# PMI_Action_bumpers.net
KiCad netlist of a schematic drawn in Altium Designer
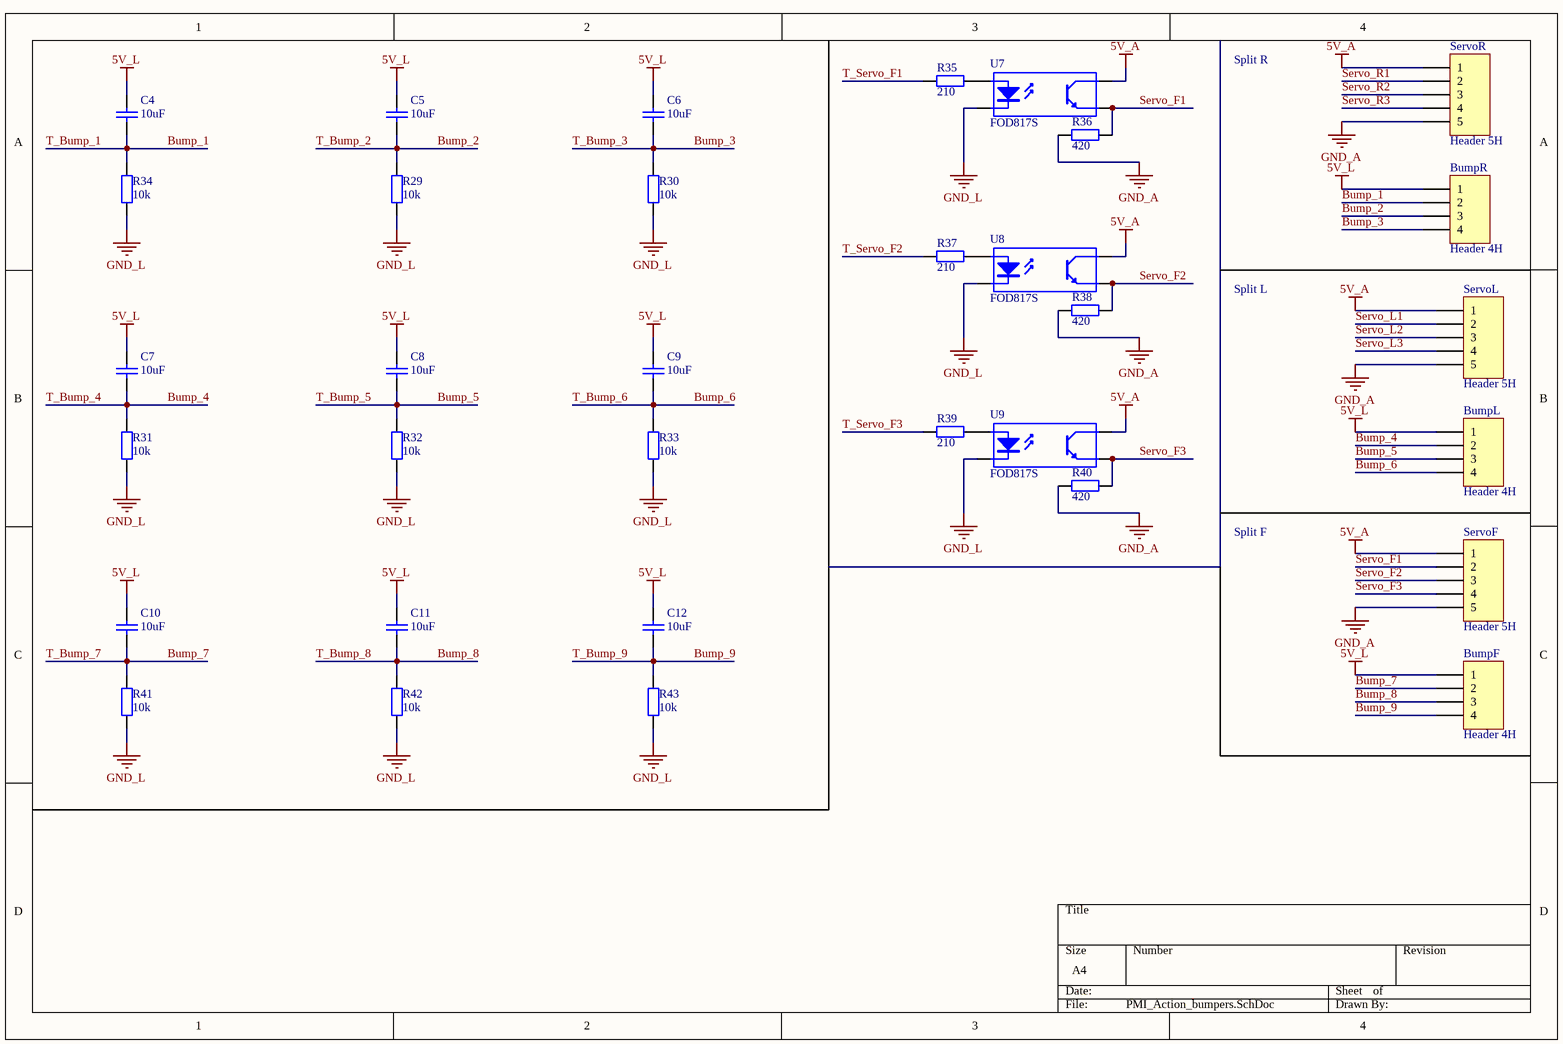
[diagram p0: PMI_Action_bumpers.SchDoc]

(export (version "E")
  (design (tool "Eeschema 10.0.6"))
  (components
    (comp (ref "BumpF")
      (value "Header 4H")
      (footprint "S4B-XH-A")
      (description "Header, 4-Pin, Right Angle")
      (fields (field (name "PUBLISHER") "Altium Limited"))
      (libsource (lib "Miscellaneous Connectors") (part "Header 4H"))
    )
    (comp (ref "BumpL")
      (value "Header 4H")
      (footprint "S4B-XH-A")
      (description "Header, 4-Pin, Right Angle")
      (fields (field (name "PUBLISHER") "Altium Limited"))
      (libsource (lib "Miscellaneous Connectors") (part "Header 4H"))
    )
    (comp (ref "BumpR")
      (value "Header 4H")
      (footprint "S4B-XH-A")
      (description "Header, 4-Pin, Right Angle")
      (fields (field (name "PUBLISHER") "Altium Limited"))
      (libsource (lib "Miscellaneous Connectors") (part "Header 4H"))
    )
    (comp (ref "C4")
      (value "10uF")
      (footprint "Capacitor 1206")
      (description "Capacitor")
      (fields (field (name "Comment") "(optional)") (field (name "PUBLISHER") "Altium Limited"))
      (libsource (lib "Miscellaneous Devices") (part "Cap"))
    )
    (comp (ref "C5")
      (value "10uF")
      (footprint "Capacitor 1206")
      (description "Capacitor")
      (fields (field (name "Comment") "(optional)") (field (name "PUBLISHER") "Altium Limited"))
      (libsource (lib "Miscellaneous Devices") (part "Cap"))
    )
    (comp (ref "C6")
      (value "10uF")
      (footprint "Capacitor 1206")
      (description "Capacitor")
      (fields (field (name "Comment") "(optional)") (field (name "PUBLISHER") "Altium Limited"))
      (libsource (lib "Miscellaneous Devices") (part "Cap"))
    )
    (comp (ref "C7")
      (value "10uF")
      (footprint "Capacitor 1206")
      (description "Capacitor")
      (fields (field (name "Comment") "(optional)") (field (name "PUBLISHER") "Altium Limited"))
      (libsource (lib "Miscellaneous Devices") (part "Cap"))
    )
    (comp (ref "C8")
      (value "10uF")
      (footprint "Capacitor 1206")
      (description "Capacitor")
      (fields (field (name "Comment") "(optional)") (field (name "PUBLISHER") "Altium Limited"))
      (libsource (lib "Miscellaneous Devices") (part "Cap"))
    )
    (comp (ref "C9")
      (value "10uF")
      (footprint "Capacitor 1206")
      (description "Capacitor")
      (fields (field (name "Comment") "(optional)") (field (name "PUBLISHER") "Altium Limited"))
      (libsource (lib "Miscellaneous Devices") (part "Cap"))
    )
    (comp (ref "C10")
      (value "10uF")
      (footprint "Capacitor 1206")
      (description "Capacitor")
      (fields (field (name "Comment") "(optional)") (field (name "PUBLISHER") "Altium Limited"))
      (libsource (lib "Miscellaneous Devices") (part "Cap"))
    )
    (comp (ref "C11")
      (value "10uF")
      (footprint "Capacitor 1206")
      (description "Capacitor")
      (fields (field (name "Comment") "(optional)") (field (name "PUBLISHER") "Altium Limited"))
      (libsource (lib "Miscellaneous Devices") (part "Cap"))
    )
    (comp (ref "C12")
      (value "10uF")
      (footprint "Capacitor 1206")
      (description "Capacitor")
      (fields (field (name "Comment") "(optional)") (field (name "PUBLISHER") "Altium Limited"))
      (libsource (lib "Miscellaneous Devices") (part "Cap"))
    )
    (comp (ref "R29")
      (value "10k")
      (footprint "Resistor 1206")
      (description "Resistor")
      (fields (field (name "Comment") "Res2") (field (name "PUBLISHER") "Altium Limited"))
      (libsource (lib "Miscellaneous Devices") (part "Res2"))
    )
    (comp (ref "R30")
      (value "10k")
      (footprint "Resistor 1206")
      (description "Resistor")
      (fields (field (name "Comment") "Res2") (field (name "PUBLISHER") "Altium Limited"))
      (libsource (lib "Miscellaneous Devices") (part "Res2"))
    )
    (comp (ref "R31")
      (value "10k")
      (footprint "Resistor 1206")
      (description "Resistor")
      (fields (field (name "Comment") "Res2") (field (name "PUBLISHER") "Altium Limited"))
      (libsource (lib "Miscellaneous Devices") (part "Res2"))
    )
    (comp (ref "R32")
      (value "10k")
      (footprint "Resistor 1206")
      (description "Resistor")
      (fields (field (name "Comment") "Res2") (field (name "PUBLISHER") "Altium Limited"))
      (libsource (lib "Miscellaneous Devices") (part "Res2"))
    )
    (comp (ref "R33")
      (value "10k")
      (footprint "Resistor 1206")
      (description "Resistor")
      (fields (field (name "Comment") "Res2") (field (name "PUBLISHER") "Altium Limited"))
      (libsource (lib "Miscellaneous Devices") (part "Res2"))
    )
    (comp (ref "R34")
      (value "10k")
      (footprint "Resistor 1206")
      (description "Resistor")
      (fields (field (name "Comment") "Res2") (field (name "PUBLISHER") "Altium Limited"))
      (libsource (lib "Miscellaneous Devices") (part "Res2"))
    )
    (comp (ref "R35")
      (value "210")
      (footprint "Resistor 1206")
      (description "Resistor")
      (fields (field (name "Comment") "Res2") (field (name "PUBLISHER") "Altium Limited"))
      (libsource (lib "") (part "Res2_1"))
    )
    (comp (ref "R36")
      (value "420")
      (footprint "Resistor 1206")
      (description "Resistor")
      (fields (field (name "Comment") "Res2") (field (name "PUBLISHER") "Altium Limited"))
      (libsource (lib "") (part "Res2_1"))
    )
    (comp (ref "R37")
      (value "210")
      (footprint "Resistor 1206")
      (description "Resistor")
      (fields (field (name "Comment") "Res2") (field (name "PUBLISHER") "Altium Limited"))
      (libsource (lib "") (part "Res2_1"))
    )
    (comp (ref "R38")
      (value "420")
      (footprint "Resistor 1206")
      (description "Resistor")
      (fields (field (name "Comment") "Res2") (field (name "PUBLISHER") "Altium Limited"))
      (libsource (lib "") (part "Res2_1"))
    )
    (comp (ref "R39")
      (value "210")
      (footprint "Resistor 1206")
      (description "Resistor")
      (fields (field (name "Comment") "Res2") (field (name "PUBLISHER") "Altium Limited"))
      (libsource (lib "") (part "Res2_1"))
    )
    (comp (ref "R40")
      (value "420")
      (footprint "Resistor 1206")
      (description "Resistor")
      (fields (field (name "Comment") "Res2") (field (name "PUBLISHER") "Altium Limited"))
      (libsource (lib "") (part "Res2_1"))
    )
    (comp (ref "R41")
      (value "10k")
      (footprint "Resistor 1206")
      (description "Resistor")
      (fields (field (name "Comment") "Res2") (field (name "PUBLISHER") "Altium Limited"))
      (libsource (lib "Miscellaneous Devices") (part "Res2"))
    )
    (comp (ref "R42")
      (value "10k")
      (footprint "Resistor 1206")
      (description "Resistor")
      (fields (field (name "Comment") "Res2") (field (name "PUBLISHER") "Altium Limited"))
      (libsource (lib "Miscellaneous Devices") (part "Res2"))
    )
    (comp (ref "R43")
      (value "10k")
      (footprint "Resistor 1206")
      (description "Resistor")
      (fields (field (name "Comment") "Res2") (field (name "PUBLISHER") "Altium Limited"))
      (libsource (lib "Miscellaneous Devices") (part "Res2"))
    )
    (comp (ref "ServoF")
      (value "Header 5H")
      (footprint "S5B-XH-A")
      (description "Header, 5-Pin, Right Angle")
      (fields (field (name "PUBLISHER") "Altium Limited"))
      (libsource (lib "Miscellaneous Connectors") (part "Header 5H"))
    )
    (comp (ref "ServoL")
      (value "Header 5H")
      (footprint "S5B-XH-A")
      (description "Header, 5-Pin, Right Angle")
      (fields (field (name "PUBLISHER") "Altium Limited"))
      (libsource (lib "Miscellaneous Connectors") (part "Header 5H"))
    )
    (comp (ref "ServoR")
      (value "Header 5H")
      (footprint "S5B-XH-A")
      (description "Header, 5-Pin, Right Angle")
      (fields (field (name "PUBLISHER") "Altium Limited"))
      (libsource (lib "Miscellaneous Connectors") (part "Header 5H"))
    )
    (comp (ref "U7")
      (value "FOD817S")
      (footprint "SOP254P1016X385-4N")
      (description "4-Pin Phototransistor Optocoupler")
      (fields (field (name "PUBLISHER") "Altium Limited"))
      (libsource (lib "Miscellaneous Devices") (part "Optoisolator1"))
    )
    (comp (ref "U8")
      (value "FOD817S")
      (footprint "SOP254P1016X385-4N")
      (description "4-Pin Phototransistor Optocoupler")
      (fields (field (name "PUBLISHER") "Altium Limited"))
      (libsource (lib "Miscellaneous Devices") (part "Optoisolator1"))
    )
    (comp (ref "U9")
      (value "FOD817S")
      (footprint "SOP254P1016X385-4N")
      (description "4-Pin Phototransistor Optocoupler")
      (fields (field (name "PUBLISHER") "Altium Limited"))
      (libsource (lib "Miscellaneous Devices") (part "Optoisolator1"))
    )
  )
  (nets
    (net (code "1") (name "/Bump_1") (class "Default")
      (node (ref "BumpR") (pin "2") (pinfunction "2_2") (pintype "passive"))
      (node (ref "C4") (pin "1") (pinfunction "1_1") (pintype "passive"))
      (node (ref "R34") (pin "1") (pinfunction "1_1") (pintype "passive"))
    )
    (net (code "2") (name "/Bump_2") (class "Default")
      (node (ref "BumpR") (pin "3") (pinfunction "3_3") (pintype "passive"))
      (node (ref "C5") (pin "1") (pinfunction "1_1") (pintype "passive"))
      (node (ref "R29") (pin "1") (pinfunction "1_1") (pintype "passive"))
    )
    (net (code "3") (name "/Bump_3") (class "Default")
      (node (ref "BumpR") (pin "4") (pinfunction "4_4") (pintype "passive"))
      (node (ref "C6") (pin "1") (pinfunction "1_1") (pintype "passive"))
      (node (ref "R30") (pin "1") (pinfunction "1_1") (pintype "passive"))
    )
    (net (code "4") (name "/Bump_4") (class "Default")
      (node (ref "BumpL") (pin "2") (pinfunction "2_2") (pintype "passive"))
      (node (ref "C7") (pin "1") (pinfunction "1_1") (pintype "passive"))
      (node (ref "R31") (pin "1") (pinfunction "1_1") (pintype "passive"))
    )
    (net (code "5") (name "/Bump_5") (class "Default")
      (node (ref "BumpL") (pin "3") (pinfunction "3_3") (pintype "passive"))
      (node (ref "C8") (pin "1") (pinfunction "1_1") (pintype "passive"))
      (node (ref "R32") (pin "1") (pinfunction "1_1") (pintype "passive"))
    )
    (net (code "6") (name "/Bump_6") (class "Default")
      (node (ref "BumpL") (pin "4") (pinfunction "4_4") (pintype "passive"))
      (node (ref "C9") (pin "1") (pinfunction "1_1") (pintype "passive"))
      (node (ref "R33") (pin "1") (pinfunction "1_1") (pintype "passive"))
    )
    (net (code "7") (name "/Bump_7") (class "Default")
      (node (ref "BumpF") (pin "2") (pinfunction "2_2") (pintype "passive"))
      (node (ref "C10") (pin "1") (pinfunction "1_1") (pintype "passive"))
      (node (ref "R41") (pin "1") (pinfunction "1_1") (pintype "passive"))
    )
    (net (code "8") (name "/Bump_8") (class "Default")
      (node (ref "BumpF") (pin "3") (pinfunction "3_3") (pintype "passive"))
      (node (ref "C11") (pin "1") (pinfunction "1_1") (pintype "passive"))
      (node (ref "R42") (pin "1") (pinfunction "1_1") (pintype "passive"))
    )
    (net (code "9") (name "/Bump_9") (class "Default")
      (node (ref "BumpF") (pin "4") (pinfunction "4_4") (pintype "passive"))
      (node (ref "C12") (pin "1") (pinfunction "1_1") (pintype "passive"))
      (node (ref "R43") (pin "1") (pinfunction "1_1") (pintype "passive"))
    )
    (net (code "10") (name "/Servo_F1") (class "Default")
      (node (ref "R36") (pin "1") (pinfunction "1_1") (pintype "passive"))
      (node (ref "ServoF") (pin "2") (pinfunction "2_2") (pintype "passive"))
      (node (ref "U7") (pin "3") (pinfunction "E_3") (pintype "passive"))
    )
    (net (code "11") (name "/Servo_F2") (class "Default")
      (node (ref "R38") (pin "1") (pinfunction "1_1") (pintype "passive"))
      (node (ref "ServoF") (pin "3") (pinfunction "3_3") (pintype "passive"))
      (node (ref "U8") (pin "3") (pinfunction "E_3") (pintype "passive"))
    )
    (net (code "12") (name "/Servo_F3") (class "Default")
      (node (ref "R40") (pin "1") (pinfunction "1_1") (pintype "passive"))
      (node (ref "ServoF") (pin "4") (pinfunction "4_4") (pintype "passive"))
      (node (ref "U9") (pin "3") (pinfunction "E_3") (pintype "passive"))
    )
    (net (code "13") (name "/Servo_L1") (class "Default")
      (node (ref "ServoL") (pin "2") (pinfunction "2_2") (pintype "passive"))
    )
    (net (code "14") (name "/Servo_L2") (class "Default")
      (node (ref "ServoL") (pin "3") (pinfunction "3_3") (pintype "passive"))
    )
    (net (code "15") (name "/Servo_L3") (class "Default")
      (node (ref "ServoL") (pin "4") (pinfunction "4_4") (pintype "passive"))
    )
    (net (code "16") (name "/Servo_R1") (class "Default")
      (node (ref "ServoR") (pin "2") (pinfunction "2_2") (pintype "passive"))
    )
    (net (code "17") (name "/Servo_R2") (class "Default")
      (node (ref "ServoR") (pin "3") (pinfunction "3_3") (pintype "passive"))
    )
    (net (code "18") (name "/Servo_R3") (class "Default")
      (node (ref "ServoR") (pin "4") (pinfunction "4_4") (pintype "passive"))
    )
    (net (code "19") (name "/T_Servo_F1") (class "Default")
      (node (ref "R35") (pin "2") (pinfunction "2_2") (pintype "passive"))
    )
    (net (code "20") (name "/T_Servo_F2") (class "Default")
      (node (ref "R37") (pin "2") (pinfunction "2_2") (pintype "passive"))
    )
    (net (code "21") (name "/T_Servo_F3") (class "Default")
      (node (ref "R39") (pin "2") (pinfunction "2_2") (pintype "passive"))
    )
    (net (code "22") (name "5V_A") (class "Default")
      (node (ref "ServoF") (pin "1") (pinfunction "1_1") (pintype "passive"))
      (node (ref "ServoL") (pin "1") (pinfunction "1_1") (pintype "passive"))
      (node (ref "ServoR") (pin "1") (pinfunction "1_1") (pintype "passive"))
      (node (ref "U7") (pin "4") (pinfunction "C_4") (pintype "passive"))
      (node (ref "U8") (pin "4") (pinfunction "C_4") (pintype "passive"))
      (node (ref "U9") (pin "4") (pinfunction "C_4") (pintype "passive"))
    )
    (net (code "23") (name "5V_L") (class "Default")
      (node (ref "BumpF") (pin "1") (pinfunction "1_1") (pintype "passive"))
      (node (ref "BumpL") (pin "1") (pinfunction "1_1") (pintype "passive"))
      (node (ref "BumpR") (pin "1") (pinfunction "1_1") (pintype "passive"))
      (node (ref "C10") (pin "2") (pinfunction "2_2") (pintype "passive"))
      (node (ref "C11") (pin "2") (pinfunction "2_2") (pintype "passive"))
      (node (ref "C12") (pin "2") (pinfunction "2_2") (pintype "passive"))
      (node (ref "C4") (pin "2") (pinfunction "2_2") (pintype "passive"))
      (node (ref "C5") (pin "2") (pinfunction "2_2") (pintype "passive"))
      (node (ref "C6") (pin "2") (pinfunction "2_2") (pintype "passive"))
      (node (ref "C7") (pin "2") (pinfunction "2_2") (pintype "passive"))
      (node (ref "C8") (pin "2") (pinfunction "2_2") (pintype "passive"))
      (node (ref "C9") (pin "2") (pinfunction "2_2") (pintype "passive"))
    )
    (net (code "24") (name "GND_A") (class "Default")
      (node (ref "R36") (pin "2") (pinfunction "2_2") (pintype "passive"))
      (node (ref "R38") (pin "2") (pinfunction "2_2") (pintype "passive"))
      (node (ref "R40") (pin "2") (pinfunction "2_2") (pintype "passive"))
      (node (ref "ServoF") (pin "5") (pinfunction "5_5") (pintype "passive"))
      (node (ref "ServoL") (pin "5") (pinfunction "5_5") (pintype "passive"))
      (node (ref "ServoR") (pin "5") (pinfunction "5_5") (pintype "passive"))
    )
    (net (code "25") (name "GND_L") (class "Default")
      (node (ref "R29") (pin "2") (pinfunction "2_2") (pintype "passive"))
      (node (ref "R30") (pin "2") (pinfunction "2_2") (pintype "passive"))
      (node (ref "R31") (pin "2") (pinfunction "2_2") (pintype "passive"))
      (node (ref "R32") (pin "2") (pinfunction "2_2") (pintype "passive"))
      (node (ref "R33") (pin "2") (pinfunction "2_2") (pintype "passive"))
      (node (ref "R34") (pin "2") (pinfunction "2_2") (pintype "passive"))
      (node (ref "R41") (pin "2") (pinfunction "2_2") (pintype "passive"))
      (node (ref "R42") (pin "2") (pinfunction "2_2") (pintype "passive"))
      (node (ref "R43") (pin "2") (pinfunction "2_2") (pintype "passive"))
      (node (ref "U7") (pin "2") (pinfunction "K_2") (pintype "passive"))
      (node (ref "U8") (pin "2") (pinfunction "K_2") (pintype "passive"))
      (node (ref "U9") (pin "2") (pinfunction "K_2") (pintype "passive"))
    )
    (net (code "26") (name "Net-(U7-A)") (class "Default")
      (node (ref "R35") (pin "1") (pinfunction "1_1") (pintype "passive"))
      (node (ref "U7") (pin "1") (pinfunction "A_1") (pintype "passive"))
    )
    (net (code "27") (name "Net-(U8-A)") (class "Default")
      (node (ref "R37") (pin "1") (pinfunction "1_1") (pintype "passive"))
      (node (ref "U8") (pin "1") (pinfunction "A_1") (pintype "passive"))
    )
    (net (code "28") (name "Net-(U9-A)") (class "Default")
      (node (ref "R39") (pin "1") (pinfunction "1_1") (pintype "passive"))
      (node (ref "U9") (pin "1") (pinfunction "A_1") (pintype "passive"))
    )
  )
)
